# FCC_Peripherals.net
KiCad netlist of a schematic drawn in Altium Designer
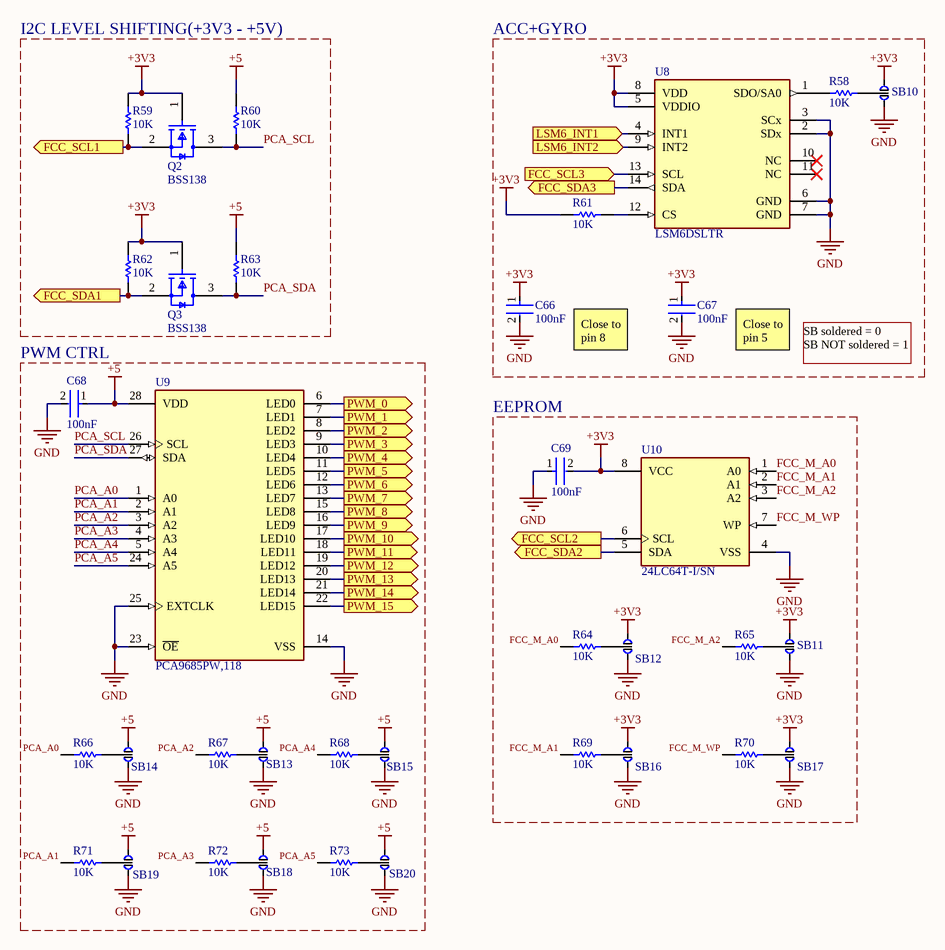
[diagram p0: FCC_Peripherals.SchDoc]

(export (version "E")
  (design (tool "Eeschema 10.0.6"))
  (components
    (comp (ref "C66")
      (value "100nF")
      (footprint "FP-CGA3E-0_3-0_1-IPC_A")
      (description "Cap Ceramic 100nF 50V X7R 10% Pad SMD 0603 +125°C Automotive T/R")
      (fields (field (name "TOLERANCE") "10%") (field (name "VOLTAGE") "50V"))
      (libsource (lib "Altium Content Vault") (part "b4654b650e69147ec39a6b967a45e02"))
    )
    (comp (ref "C67")
      (value "100nF")
      (footprint "FP-CGA3E-0_3-0_1-IPC_A")
      (description "Cap Ceramic 100nF 50V X7R 10% Pad SMD 0603 +125°C Automotive T/R")
      (fields (field (name "TOLERANCE") "10%") (field (name "VOLTAGE") "50V"))
      (libsource (lib "Altium Content Vault") (part "b4654b650e69147ec39a6b967a45e02"))
    )
    (comp (ref "C68")
      (value "100nF")
      (footprint "FP-CGA3E-0_3-0_1-IPC_A")
      (description "Cap Ceramic 100nF 50V X7R 10% Pad SMD 0603 +125°C Automotive T/R")
      (fields (field (name "TOLERANCE") "10%") (field (name "VOLTAGE") "50V"))
      (libsource (lib "Altium Content Vault") (part "b4654b650e69147ec39a6b967a45e02"))
    )
    (comp (ref "C69")
      (value "100nF")
      (footprint "FP-CGA3E-0_3-0_1-IPC_A")
      (description "Cap Ceramic 100nF 50V X7R 10% Pad SMD 0603 +125°C Automotive T/R")
      (fields (field (name "TOLERANCE") "10%") (field (name "VOLTAGE") "50V"))
      (libsource (lib "Altium Content Vault") (part "b4654b650e69147ec39a6b967a45e02"))
    )
    (comp (ref "Q2")
      (value "BSS138")
      (footprint "FP-318-08-IPC_B")
      (description "MOSFET N-CH 50V 220MA SOT-23")
      (libsource (lib "Altium Content Vault") (part "3b9c635fedb024a5347a57b145af9cc"))
    )
    (comp (ref "Q3")
      (value "BSS138")
      (footprint "FP-318-08-IPC_B")
      (description "MOSFET N-CH 50V 220MA SOT-23")
      (libsource (lib "Altium Content Vault") (part "3b9c635fedb024a5347a57b145af9cc"))
    )
    (comp (ref "R58")
      (value "10K")
      (footprint "RESC1608X55X25ML10T15")
      (description "Chip Resistor, 0 Ohm, +/- 5%, 0.1 W, -55 to 155 degC, 0603 (1608 Metric), RoHS, Tape and Reel")
      (fields (field (name "TOLERANCE") "5%") (field (name "MANUFACTURER") "Yageo"))
      (libsource (lib "Altium Content Vault") (part "RES-2"))
    )
    (comp (ref "R59")
      (value "10K")
      (footprint "RESC1608X55X25ML10T15")
      (description "Chip Resistor, 0 Ohm, +/- 5%, 0.1 W, -55 to 155 degC, 0603 (1608 Metric), RoHS, Tape and Reel")
      (fields (field (name "TOLERANCE") "5%") (field (name "MANUFACTURER") "Yageo"))
      (libsource (lib "Altium Content Vault") (part "RES-2"))
    )
    (comp (ref "R60")
      (value "10K")
      (footprint "RESC1608X55X25ML10T15")
      (description "Chip Resistor, 0 Ohm, +/- 5%, 0.1 W, -55 to 155 degC, 0603 (1608 Metric), RoHS, Tape and Reel")
      (fields (field (name "TOLERANCE") "5%") (field (name "MANUFACTURER") "Yageo"))
      (libsource (lib "Altium Content Vault") (part "RES-2"))
    )
    (comp (ref "R61")
      (value "10K")
      (footprint "RESC1608X55X25ML10T15")
      (description "Chip Resistor, 0 Ohm, +/- 5%, 0.1 W, -55 to 155 degC, 0603 (1608 Metric), RoHS, Tape and Reel")
      (fields (field (name "TOLERANCE") "5%") (field (name "MANUFACTURER") "Yageo"))
      (libsource (lib "Altium Content Vault") (part "RES-2"))
    )
    (comp (ref "R62")
      (value "10K")
      (footprint "RESC1608X55X25ML10T15")
      (description "Chip Resistor, 0 Ohm, +/- 5%, 0.1 W, -55 to 155 degC, 0603 (1608 Metric), RoHS, Tape and Reel")
      (fields (field (name "TOLERANCE") "5%") (field (name "MANUFACTURER") "Yageo"))
      (libsource (lib "Altium Content Vault") (part "RES-2"))
    )
    (comp (ref "R63")
      (value "10K")
      (footprint "RESC1608X55X25ML10T15")
      (description "Chip Resistor, 0 Ohm, +/- 5%, 0.1 W, -55 to 155 degC, 0603 (1608 Metric), RoHS, Tape and Reel")
      (fields (field (name "TOLERANCE") "5%") (field (name "MANUFACTURER") "Yageo"))
      (libsource (lib "Altium Content Vault") (part "RES-2"))
    )
    (comp (ref "R64")
      (value "10K")
      (footprint "RESC1608X55X25ML10T15")
      (description "Chip Resistor, 0 Ohm, +/- 5%, 0.1 W, -55 to 155 degC, 0603 (1608 Metric), RoHS, Tape and Reel")
      (fields (field (name "TOLERANCE") "5%") (field (name "MANUFACTURER") "Yageo"))
      (libsource (lib "Altium Content Vault") (part "RES-2"))
    )
    (comp (ref "R65")
      (value "10K")
      (footprint "RESC1608X55X25ML10T15")
      (description "Chip Resistor, 0 Ohm, +/- 5%, 0.1 W, -55 to 155 degC, 0603 (1608 Metric), RoHS, Tape and Reel")
      (fields (field (name "TOLERANCE") "5%") (field (name "MANUFACTURER") "Yageo"))
      (libsource (lib "Altium Content Vault") (part "RES-2"))
    )
    (comp (ref "R66")
      (value "10K")
      (footprint "RESC1608X55X25ML10T15")
      (description "Chip Resistor, 0 Ohm, +/- 5%, 0.1 W, -55 to 155 degC, 0603 (1608 Metric), RoHS, Tape and Reel")
      (fields (field (name "TOLERANCE") "5%") (field (name "MANUFACTURER") "Yageo"))
      (libsource (lib "Altium Content Vault") (part "RES-2"))
    )
    (comp (ref "R67")
      (value "10K")
      (footprint "RESC1608X55X25ML10T15")
      (description "Chip Resistor, 0 Ohm, +/- 5%, 0.1 W, -55 to 155 degC, 0603 (1608 Metric), RoHS, Tape and Reel")
      (fields (field (name "TOLERANCE") "5%") (field (name "MANUFACTURER") "Yageo"))
      (libsource (lib "Altium Content Vault") (part "RES-2"))
    )
    (comp (ref "R68")
      (value "10K")
      (footprint "RESC1608X55X25ML10T15")
      (description "Chip Resistor, 0 Ohm, +/- 5%, 0.1 W, -55 to 155 degC, 0603 (1608 Metric), RoHS, Tape and Reel")
      (fields (field (name "TOLERANCE") "5%") (field (name "MANUFACTURER") "Yageo"))
      (libsource (lib "Altium Content Vault") (part "RES-2"))
    )
    (comp (ref "R69")
      (value "10K")
      (footprint "RESC1608X55X25ML10T15")
      (description "Chip Resistor, 0 Ohm, +/- 5%, 0.1 W, -55 to 155 degC, 0603 (1608 Metric), RoHS, Tape and Reel")
      (fields (field (name "TOLERANCE") "5%") (field (name "MANUFACTURER") "Yageo"))
      (libsource (lib "Altium Content Vault") (part "RES-2"))
    )
    (comp (ref "R70")
      (value "10K")
      (footprint "RESC1608X55X25ML10T15")
      (description "Chip Resistor, 0 Ohm, +/- 5%, 0.1 W, -55 to 155 degC, 0603 (1608 Metric), RoHS, Tape and Reel")
      (fields (field (name "TOLERANCE") "5%") (field (name "MANUFACTURER") "Yageo"))
      (libsource (lib "Altium Content Vault") (part "RES-2"))
    )
    (comp (ref "R71")
      (value "10K")
      (footprint "RESC1608X55X25ML10T15")
      (description "Chip Resistor, 0 Ohm, +/- 5%, 0.1 W, -55 to 155 degC, 0603 (1608 Metric), RoHS, Tape and Reel")
      (fields (field (name "TOLERANCE") "5%") (field (name "MANUFACTURER") "Yageo"))
      (libsource (lib "Altium Content Vault") (part "RES-2"))
    )
    (comp (ref "R72")
      (value "10K")
      (footprint "RESC1608X55X25ML10T15")
      (description "Chip Resistor, 0 Ohm, +/- 5%, 0.1 W, -55 to 155 degC, 0603 (1608 Metric), RoHS, Tape and Reel")
      (fields (field (name "TOLERANCE") "5%") (field (name "MANUFACTURER") "Yageo"))
      (libsource (lib "Altium Content Vault") (part "RES-2"))
    )
    (comp (ref "R73")
      (value "10K")
      (footprint "RESC1608X55X25ML10T15")
      (description "Chip Resistor, 0 Ohm, +/- 5%, 0.1 W, -55 to 155 degC, 0603 (1608 Metric), RoHS, Tape and Reel")
      (fields (field (name "TOLERANCE") "5%") (field (name "MANUFACTURER") "Yageo"))
      (libsource (lib "Altium Content Vault") (part "RES-2"))
    )
    (comp (ref "SB10")
      (value "Solderbridge3P")
      (footprint "SolderBridge3P")
      (libsource (lib "Solder_Bridge") (part "Solderbridge3P"))
    )
    (comp (ref "SB11")
      (value "Solderbridge3P")
      (footprint "SolderBridge3P")
      (libsource (lib "Solder_Bridge") (part "Solderbridge3P"))
    )
    (comp (ref "SB12")
      (value "Solderbridge3P")
      (footprint "SolderBridge3P")
      (libsource (lib "Solder_Bridge") (part "Solderbridge3P"))
    )
    (comp (ref "SB13")
      (value "Solderbridge3P")
      (footprint "SolderBridge3P")
      (libsource (lib "Solder_Bridge") (part "Solderbridge3P"))
    )
    (comp (ref "SB14")
      (value "Solderbridge3P")
      (footprint "SolderBridge3P")
      (libsource (lib "Solder_Bridge") (part "Solderbridge3P"))
    )
    (comp (ref "SB15")
      (value "Solderbridge3P")
      (footprint "SolderBridge3P")
      (libsource (lib "Solder_Bridge") (part "Solderbridge3P"))
    )
    (comp (ref "SB16")
      (value "Solderbridge3P")
      (footprint "SolderBridge3P")
      (libsource (lib "Solder_Bridge") (part "Solderbridge3P"))
    )
    (comp (ref "SB17")
      (value "Solderbridge3P")
      (footprint "SolderBridge3P")
      (libsource (lib "Solder_Bridge") (part "Solderbridge3P"))
    )
    (comp (ref "SB18")
      (value "Solderbridge3P")
      (footprint "SolderBridge3P")
      (libsource (lib "Solder_Bridge") (part "Solderbridge3P"))
    )
    (comp (ref "SB19")
      (value "Solderbridge3P")
      (footprint "SolderBridge3P")
      (libsource (lib "Solder_Bridge") (part "Solderbridge3P"))
    )
    (comp (ref "SB20")
      (value "Solderbridge3P")
      (footprint "SolderBridge3P")
      (libsource (lib "Solder_Bridge") (part "Solderbridge3P"))
    )
    (comp (ref "U8")
      (value "LSM6DSLTR")
      (footprint "FP-LGA-14L-DM00249496-MFG")
      (description "IMU ACCEL/GYRO I2C/SPI 14LGA")
      (fields
        (field (name "MANUFACTURER") "STMicroelectronics")
        (field (name "OCTOPART") "https://octopart.com/lsm6dsltr-stmicroelectronics-66358193")
      )
      (libsource (lib "Altium Content Vault") (part "4e27e7d1829efda5344af1708d65448"))
    )
    (comp (ref "U9")
      (value "PCA9685PW,118")
      (footprint "FP-SOT361-1-MFG")
      (description "IC LED DRIVER RGBA 28-TSSOP")
      (fields
        (field (name "MANUFACTURER") "NXP Semiconductors")
        (field (name "OCTOPART") "https://octopart.com/pca9685pw%2C118-nxp+semiconductors-11853435")
      )
      (libsource (lib "Altium Content Vault") (part "50b6f6febb80a1ca83d1eae7256368c"))
    )
    (comp (ref "U10")
      (value "24LC64T-I/SN")
      (footprint "FP-C04-057-SN-MFG")
      (description "IC EEPROM 64K I2C 400KHZ 8SOIC")
      (fields
        (field (name "OCTOPART") "https://octopart.com/24lc64t-i%2Fsn-microchip-451854")
        (field (name "MANUFACTURER") "Microchip Technology")
      )
      (libsource (lib "Altium Content Vault") (part "aa9a952ee66a023cd78eade27961581"))
    )
  )
  (nets
    (net (code "1") (name "+3V3") (class "Default")
      (node (ref "C66") (pin "1") (pinfunction "1_1") (pintype "passive"))
      (node (ref "C67") (pin "1") (pinfunction "1_1") (pintype "passive"))
      (node (ref "C69") (pin "2") (pinfunction "2_2") (pintype "passive"))
      (node (ref "Q2") (pin "1") (pinfunction "G_1") (pintype "passive"))
      (node (ref "Q3") (pin "1") (pinfunction "G_1") (pintype "passive"))
      (node (ref "R59") (pin "2") (pinfunction "2_2") (pintype "passive"))
      (node (ref "R61") (pin "1") (pinfunction "1_1") (pintype "passive"))
      (node (ref "R62") (pin "2") (pinfunction "2_2") (pintype "passive"))
      (node (ref "SB10") (pin "1") (pinfunction "1_1") (pintype "passive"))
      (node (ref "SB11") (pin "1") (pinfunction "1_1") (pintype "passive"))
      (node (ref "SB12") (pin "1") (pinfunction "1_1") (pintype "passive"))
      (node (ref "SB16") (pin "1") (pinfunction "1_1") (pintype "passive"))
      (node (ref "SB17") (pin "1") (pinfunction "1_1") (pintype "passive"))
      (node (ref "U10") (pin "8") (pinfunction "VCC_8") (pintype "power_in"))
      (node (ref "U8") (pin "5") (pinfunction "VDDIO_5") (pintype "power_in"))
      (node (ref "U8") (pin "8") (pinfunction "VDD_8") (pintype "power_in"))
    )
    (net (code "2") (name "+5") (class "Default")
      (node (ref "C68") (pin "1") (pinfunction "1_1") (pintype "passive"))
      (node (ref "R60") (pin "2") (pinfunction "2_2") (pintype "passive"))
      (node (ref "R63") (pin "2") (pinfunction "2_2") (pintype "passive"))
      (node (ref "SB13") (pin "1") (pinfunction "1_1") (pintype "passive"))
      (node (ref "SB14") (pin "1") (pinfunction "1_1") (pintype "passive"))
      (node (ref "SB15") (pin "1") (pinfunction "1_1") (pintype "passive"))
      (node (ref "SB18") (pin "1") (pinfunction "1_1") (pintype "passive"))
      (node (ref "SB19") (pin "1") (pinfunction "1_1") (pintype "passive"))
      (node (ref "SB20") (pin "1") (pinfunction "1_1") (pintype "passive"))
      (node (ref "U9") (pin "28") (pinfunction "VDD_28") (pintype "power_in"))
    )
    (net (code "3") (name "/FCC_M_A0") (class "Default")
      (node (ref "R64") (pin "2") (pinfunction "2_2") (pintype "passive"))
      (node (ref "U10") (pin "1") (pinfunction "A0_1") (pintype "input"))
    )
    (net (code "4") (name "/FCC_M_A1") (class "Default")
      (node (ref "R69") (pin "2") (pinfunction "2_2") (pintype "passive"))
      (node (ref "U10") (pin "2") (pinfunction "A1_2") (pintype "input"))
    )
    (net (code "5") (name "/FCC_M_A2") (class "Default")
      (node (ref "R65") (pin "2") (pinfunction "2_2") (pintype "passive"))
      (node (ref "U10") (pin "3") (pinfunction "A2_3") (pintype "input"))
    )
    (net (code "6") (name "/FCC_M_WP") (class "Default")
      (node (ref "R70") (pin "2") (pinfunction "2_2") (pintype "passive"))
      (node (ref "U10") (pin "7") (pinfunction "WP_7") (pintype "input"))
    )
    (net (code "7") (name "/FCC_SCL1") (class "Default")
      (node (ref "Q2") (pin "2") (pinfunction "S_2") (pintype "passive"))
      (node (ref "R59") (pin "1") (pinfunction "1_1") (pintype "passive"))
    )
    (net (code "8") (name "/FCC_SCL2") (class "Default")
      (node (ref "U10") (pin "6") (pinfunction "SCL_6") (pintype "open_collector"))
    )
    (net (code "9") (name "/FCC_SCL3") (class "Default")
      (node (ref "U8") (pin "13") (pinfunction "SCL_13") (pintype "input"))
    )
    (net (code "10") (name "/FCC_SDA1") (class "Default")
      (node (ref "Q3") (pin "2") (pinfunction "S_2") (pintype "passive"))
      (node (ref "R62") (pin "1") (pinfunction "1_1") (pintype "passive"))
    )
    (net (code "11") (name "/FCC_SDA2") (class "Default")
      (node (ref "U10") (pin "5") (pinfunction "SDA_5") (pintype "open_collector"))
    )
    (net (code "12") (name "/FCC_SDA3") (class "Default")
      (node (ref "U8") (pin "14") (pinfunction "SDA_14") (pintype "output"))
    )
    (net (code "13") (name "/LSM6_INT1") (class "Default")
      (node (ref "U8") (pin "4") (pinfunction "INT1_4") (pintype "input"))
    )
    (net (code "14") (name "/LSM6_INT2") (class "Default")
      (node (ref "U8") (pin "9") (pinfunction "INT2_9") (pintype "input"))
    )
    (net (code "15") (name "/PCA_A0") (class "Default")
      (node (ref "R66") (pin "1") (pinfunction "1_1") (pintype "passive"))
      (node (ref "U9") (pin "1") (pinfunction "A0_1") (pintype "input"))
    )
    (net (code "16") (name "/PCA_A1") (class "Default")
      (node (ref "R71") (pin "1") (pinfunction "1_1") (pintype "passive"))
      (node (ref "U9") (pin "2") (pinfunction "A1_2") (pintype "input"))
    )
    (net (code "17") (name "/PCA_A2") (class "Default")
      (node (ref "R67") (pin "1") (pinfunction "1_1") (pintype "passive"))
      (node (ref "U9") (pin "3") (pinfunction "A2_3") (pintype "input"))
    )
    (net (code "18") (name "/PCA_A3") (class "Default")
      (node (ref "R72") (pin "1") (pinfunction "1_1") (pintype "passive"))
      (node (ref "U9") (pin "4") (pinfunction "A3_4") (pintype "input"))
    )
    (net (code "19") (name "/PCA_A4") (class "Default")
      (node (ref "R68") (pin "1") (pinfunction "1_1") (pintype "passive"))
      (node (ref "U9") (pin "5") (pinfunction "A4_5") (pintype "input"))
    )
    (net (code "20") (name "/PCA_A5") (class "Default")
      (node (ref "R73") (pin "1") (pinfunction "1_1") (pintype "passive"))
      (node (ref "U9") (pin "24") (pinfunction "A5_24") (pintype "input"))
    )
    (net (code "21") (name "/PCA_SCL") (class "Default")
      (node (ref "Q2") (pin "3") (pinfunction "D_3") (pintype "passive"))
      (node (ref "R60") (pin "1") (pinfunction "1_1") (pintype "passive"))
      (node (ref "U9") (pin "26") (pinfunction "SCL_26") (pintype "input"))
    )
    (net (code "22") (name "/PCA_SDA") (class "Default")
      (node (ref "Q3") (pin "3") (pinfunction "D_3") (pintype "passive"))
      (node (ref "R63") (pin "1") (pinfunction "1_1") (pintype "passive"))
      (node (ref "U9") (pin "27") (pinfunction "SDA_27") (pintype "bidirectional"))
    )
    (net (code "23") (name "/PWM_0") (class "Default")
      (node (ref "U9") (pin "6") (pinfunction "LED0_6") (pintype "passive"))
    )
    (net (code "24") (name "/PWM_1") (class "Default")
      (node (ref "U9") (pin "7") (pinfunction "LED1_7") (pintype "passive"))
    )
    (net (code "25") (name "/PWM_2") (class "Default")
      (node (ref "U9") (pin "8") (pinfunction "LED2_8") (pintype "passive"))
    )
    (net (code "26") (name "/PWM_3") (class "Default")
      (node (ref "U9") (pin "9") (pinfunction "LED3_9") (pintype "passive"))
    )
    (net (code "27") (name "/PWM_4") (class "Default")
      (node (ref "U9") (pin "10") (pinfunction "LED4_10") (pintype "passive"))
    )
    (net (code "28") (name "/PWM_5") (class "Default")
      (node (ref "U9") (pin "11") (pinfunction "LED5_11") (pintype "passive"))
    )
    (net (code "29") (name "/PWM_6") (class "Default")
      (node (ref "U9") (pin "12") (pinfunction "LED6_12") (pintype "passive"))
    )
    (net (code "30") (name "/PWM_7") (class "Default")
      (node (ref "U9") (pin "13") (pinfunction "LED7_13") (pintype "passive"))
    )
    (net (code "31") (name "/PWM_8") (class "Default")
      (node (ref "U9") (pin "15") (pinfunction "LED8_15") (pintype "passive"))
    )
    (net (code "32") (name "/PWM_9") (class "Default")
      (node (ref "U9") (pin "16") (pinfunction "LED9_16") (pintype "passive"))
    )
    (net (code "33") (name "/PWM_10") (class "Default")
      (node (ref "U9") (pin "17") (pinfunction "LED10_17") (pintype "passive"))
    )
    (net (code "34") (name "/PWM_11") (class "Default")
      (node (ref "U9") (pin "18") (pinfunction "LED11_18") (pintype "passive"))
    )
    (net (code "35") (name "/PWM_12") (class "Default")
      (node (ref "U9") (pin "19") (pinfunction "LED12_19") (pintype "passive"))
    )
    (net (code "36") (name "/PWM_13") (class "Default")
      (node (ref "U9") (pin "20") (pinfunction "LED13_20") (pintype "passive"))
    )
    (net (code "37") (name "/PWM_14") (class "Default")
      (node (ref "U9") (pin "21") (pinfunction "LED14_21") (pintype "passive"))
    )
    (net (code "38") (name "/PWM_15") (class "Default")
      (node (ref "U9") (pin "22") (pinfunction "LED15_22") (pintype "passive"))
    )
    (net (code "39") (name "GND") (class "Default")
      (node (ref "C66") (pin "2") (pinfunction "2_2") (pintype "passive"))
      (node (ref "C67") (pin "2") (pinfunction "2_2") (pintype "passive"))
      (node (ref "C68") (pin "2") (pinfunction "2_2") (pintype "passive"))
      (node (ref "C69") (pin "1") (pinfunction "1_1") (pintype "passive"))
      (node (ref "SB10") (pin "2") (pinfunction "2_2") (pintype "passive"))
      (node (ref "SB11") (pin "2") (pinfunction "2_2") (pintype "passive"))
      (node (ref "SB12") (pin "2") (pinfunction "2_2") (pintype "passive"))
      (node (ref "SB13") (pin "2") (pinfunction "2_2") (pintype "passive"))
      (node (ref "SB14") (pin "2") (pinfunction "2_2") (pintype "passive"))
      (node (ref "SB15") (pin "2") (pinfunction "2_2") (pintype "passive"))
      (node (ref "SB16") (pin "2") (pinfunction "2_2") (pintype "passive"))
      (node (ref "SB17") (pin "2") (pinfunction "2_2") (pintype "passive"))
      (node (ref "SB18") (pin "2") (pinfunction "2_2") (pintype "passive"))
      (node (ref "SB19") (pin "2") (pinfunction "2_2") (pintype "passive"))
      (node (ref "SB20") (pin "2") (pinfunction "2_2") (pintype "passive"))
      (node (ref "U10") (pin "4") (pinfunction "VSS_4") (pintype "power_in"))
      (node (ref "U8") (pin "2") (pinfunction "SDx_2") (pintype "passive"))
      (node (ref "U8") (pin "3") (pinfunction "SCx_3") (pintype "passive"))
      (node (ref "U8") (pin "6") (pinfunction "GND_6") (pintype "power_in"))
      (node (ref "U8") (pin "7") (pinfunction "GND_7") (pintype "power_in"))
      (node (ref "U9") (pin "14") (pinfunction "VSS_14") (pintype "power_in"))
      (node (ref "U9") (pin "23") (pinfunction "~{OE}_23") (pintype "input"))
      (node (ref "U9") (pin "25") (pinfunction "EXTCLK_25") (pintype "input"))
    )
    (net (code "40") (name "Net-(R58-Pad2)") (class "Default")
      (node (ref "R58") (pin "2") (pinfunction "2_2") (pintype "passive"))
      (node (ref "SB10") (pin "3") (pinfunction "3_3") (pintype "power_in"))
    )
    (net (code "41") (name "Net-(R64-Pad1)") (class "Default")
      (node (ref "R64") (pin "1") (pinfunction "1_1") (pintype "passive"))
      (node (ref "SB12") (pin "3") (pinfunction "3_3") (pintype "power_in"))
    )
    (net (code "42") (name "Net-(R65-Pad1)") (class "Default")
      (node (ref "R65") (pin "1") (pinfunction "1_1") (pintype "passive"))
      (node (ref "SB11") (pin "3") (pinfunction "3_3") (pintype "power_in"))
    )
    (net (code "43") (name "Net-(R66-Pad2)") (class "Default")
      (node (ref "R66") (pin "2") (pinfunction "2_2") (pintype "passive"))
      (node (ref "SB14") (pin "3") (pinfunction "3_3") (pintype "power_in"))
    )
    (net (code "44") (name "Net-(R67-Pad2)") (class "Default")
      (node (ref "R67") (pin "2") (pinfunction "2_2") (pintype "passive"))
      (node (ref "SB13") (pin "3") (pinfunction "3_3") (pintype "power_in"))
    )
    (net (code "45") (name "Net-(R68-Pad2)") (class "Default")
      (node (ref "R68") (pin "2") (pinfunction "2_2") (pintype "passive"))
      (node (ref "SB15") (pin "3") (pinfunction "3_3") (pintype "power_in"))
    )
    (net (code "46") (name "Net-(R69-Pad1)") (class "Default")
      (node (ref "R69") (pin "1") (pinfunction "1_1") (pintype "passive"))
      (node (ref "SB16") (pin "3") (pinfunction "3_3") (pintype "power_in"))
    )
    (net (code "47") (name "Net-(R70-Pad1)") (class "Default")
      (node (ref "R70") (pin "1") (pinfunction "1_1") (pintype "passive"))
      (node (ref "SB17") (pin "3") (pinfunction "3_3") (pintype "power_in"))
    )
    (net (code "48") (name "Net-(R71-Pad2)") (class "Default")
      (node (ref "R71") (pin "2") (pinfunction "2_2") (pintype "passive"))
      (node (ref "SB19") (pin "3") (pinfunction "3_3") (pintype "power_in"))
    )
    (net (code "49") (name "Net-(R72-Pad2)") (class "Default")
      (node (ref "R72") (pin "2") (pinfunction "2_2") (pintype "passive"))
      (node (ref "SB18") (pin "3") (pinfunction "3_3") (pintype "power_in"))
    )
    (net (code "50") (name "Net-(R73-Pad2)") (class "Default")
      (node (ref "R73") (pin "2") (pinfunction "2_2") (pintype "passive"))
      (node (ref "SB20") (pin "3") (pinfunction "3_3") (pintype "power_in"))
    )
    (net (code "51") (name "Net-(U8-CS)") (class "Default")
      (node (ref "R61") (pin "2") (pinfunction "2_2") (pintype "passive"))
      (node (ref "U8") (pin "12") (pinfunction "CS_12") (pintype "input"))
    )
    (net (code "52") (name "Net-(U8-SDO{slash}SA0)") (class "Default")
      (node (ref "R58") (pin "1") (pinfunction "1_1") (pintype "passive"))
      (node (ref "U8") (pin "1") (pinfunction "SDO/SA0_1") (pintype "output"))
    )
    (net (code "53") (name "unconnected-(U8-NC-Pad10)") (class "Default")
      (node (ref "U8") (pin "10") (pinfunction "NC_10") (pintype "passive+no_connect"))
    )
    (net (code "54") (name "unconnected-(U8-NC-Pad11)") (class "Default")
      (node (ref "U8") (pin "11") (pinfunction "NC_11") (pintype "passive+no_connect"))
    )
  )
)
